# Power.net
KiCad netlist of a schematic drawn in Altium Designer
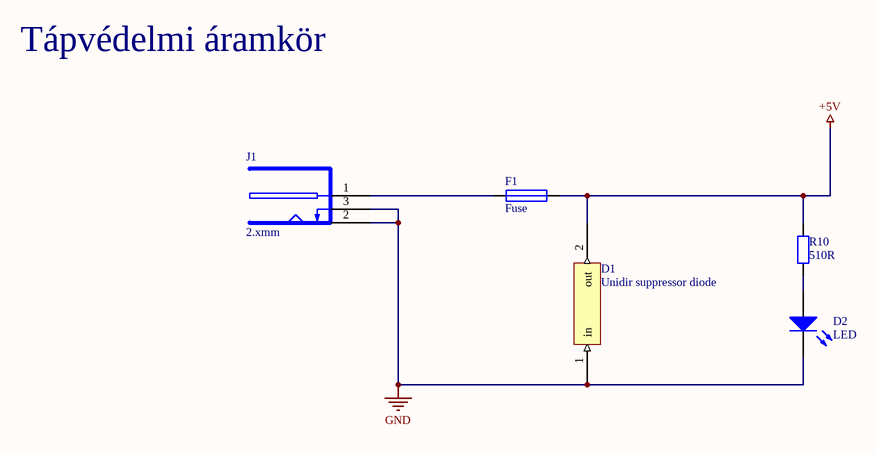
[diagram p0: Power.SchDoc]

(export (version "E")
  (design (tool "Eeschema 10.0.6"))
  (components
    (comp (ref "D1")
      (value "Unidir suppressor diode")
      (footprint "DIOM4426X23M")
      (description "Suppressor diode for transients")
      (libsource (lib "hallglib") (part "Suppressor diode"))
    )
    (comp (ref "D2")
      (value "LED")
      (footprint "FP_0805_LED_RED")
      (description "Typical RED GaAs LED")
      (libsource (lib "hallglib") (part "LED"))
    )
    (comp (ref "F1") (value "Fuse") (footprint "FP_MULTIFUSE") (libsource (lib "hallglib") (part "Fuse")))
    (comp (ref "J1")
      (value "2.xmm")
      (footprint "FP_DC_TAP_ANYA")
      (description "2.xmm DC HEBA25 TÁPFESZÜLTSÉG ALJZAT ZÁRT, NYÁKBA 90°")
      (libsource (lib "hallglib") (part "DC_TAP_ANYA"))
    )
    (comp (ref "R10")
      (value "510R")
      (footprint "FP_1206_RES")
      (description "Resistor")
      (fields (field (name "TOLERANCE") "5%") (field (name "POWER") "0.25W"))
      (libsource (lib "hallglib") (part "RES"))
    )
  )
  (nets
    (net (code "1") (name "+5V") (class "Default")
      (node (ref "D1") (pin "2") (pinfunction "out_2") (pintype "output"))
      (node (ref "F1") (pin "2") (pinfunction "2_2") (pintype "passive"))
      (node (ref "R10") (pin "2") (pinfunction "2_2") (pintype "passive"))
    )
    (net (code "2") (name "GND") (class "Default")
      (node (ref "D1") (pin "1") (pinfunction "in_1") (pintype "input"))
      (node (ref "D2") (pin "2") (pinfunction "K_2") (pintype "passive"))
      (node (ref "J1") (pin "2") (pinfunction "SLEEVE_2") (pintype "power_in"))
      (node (ref "J1") (pin "3") (pinfunction "BREAK_3") (pintype "power_in"))
    )
    (net (code "3") (name "Net-(D2-A)") (class "Default")
      (node (ref "D2") (pin "1") (pinfunction "A_1") (pintype "passive"))
      (node (ref "R10") (pin "1") (pinfunction "1_1") (pintype "passive"))
    )
    (net (code "4") (name "Net-(J1-PIN)") (class "Default")
      (node (ref "F1") (pin "1") (pinfunction "1_1") (pintype "passive"))
      (node (ref "J1") (pin "1") (pinfunction "PIN_1") (pintype "power_in"))
    )
  )
)
